# ESP8266_SMD_0603.net
KiCad netlist of a schematic drawn in EAGLE
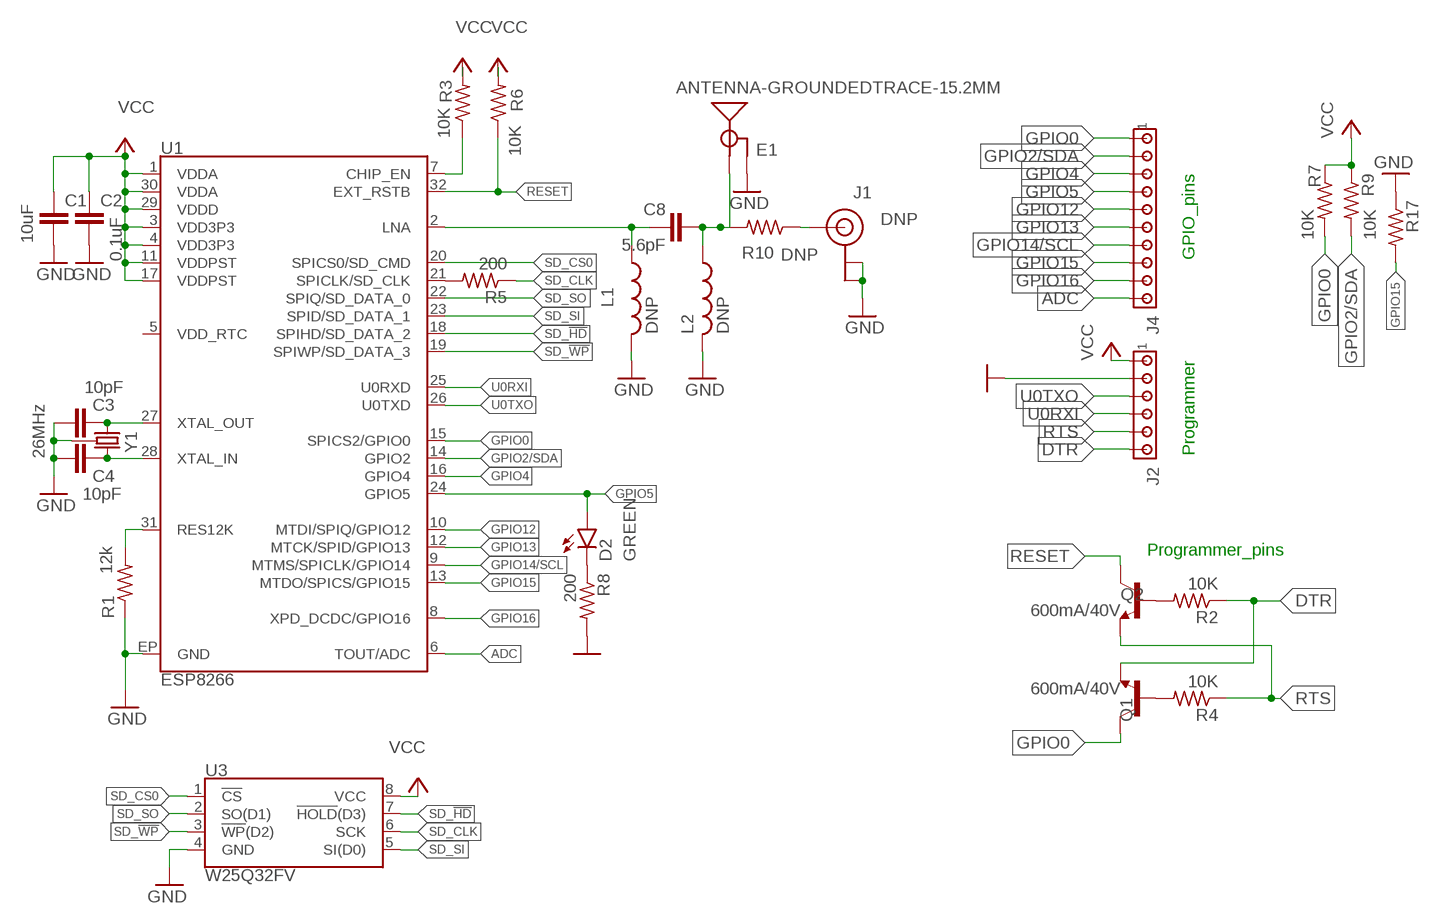
[diagram p0: schematic, sheet 1]

(export (version "E")
  (design (tool "Eeschema 10.0.6"))
  (components
    (comp (ref "C1")
      (value "10uF")
      (footprint "eagle-import:C0603")
      (libsource (lib "eagle-import") (part "resistor_C-EUC0603"))
    )
    (comp (ref "C2")
      (value "0.1uF")
      (footprint "eagle-import:C0603")
      (libsource (lib "eagle-import") (part "resistor_C-EUC0603"))
    )
    (comp (ref "C3")
      (value "10pF")
      (footprint "eagle-import:C0603")
      (libsource (lib "eagle-import") (part "C-EUC0603"))
    )
    (comp (ref "C4")
      (value "10pF")
      (footprint "eagle-import:C0603")
      (libsource (lib "eagle-import") (part "C-EUC0603"))
    )
    (comp (ref "C8")
      (value "5.6pF")
      (footprint "eagle-import:C0603")
      (libsource (lib "eagle-import") (part "C-EUC0603"))
    )
    (comp (ref "D2")
      (value "GREEN")
      (footprint "eagle-import:LED-0603")
      (libsource (lib "eagle-import") (part "LED-GREEN0603"))
    )
    (comp (ref "E1")
      (value "ANTENNA-GROUNDEDTRACE-15.2MM")
      (footprint "eagle-import:TRACE_ANTENNA_2.4GHZ_15.2MM")
      (libsource (lib "eagle-import") (part "ANTENNA-GROUNDEDTRACE-15.2MM"))
    )
    (comp (ref "J1")
      (value "DNP")
      (footprint "eagle-import:U.FL")
      (libsource (lib "eagle-import") (part "U.FL"))
    )
    (comp (ref "J2")
      (value "MTA06-100")
      (footprint "eagle-import:10X06MTA")
      (libsource (lib "eagle-import") (part "MTA06-100"))
    )
    (comp (ref "J4")
      (value "MTA10-100")
      (footprint "eagle-import:10X10MTA")
      (libsource (lib "eagle-import") (part "MTA10-100"))
    )
    (comp (ref "L1")
      (value "DNP")
      (footprint "eagle-import:L0603")
      (libsource (lib "eagle-import") (part "L-USL0603"))
    )
    (comp (ref "L2")
      (value "DNP")
      (footprint "eagle-import:L0603")
      (libsource (lib "eagle-import") (part "L-USL0603"))
    )
    (comp (ref "Q1")
      (value "600mA/40V")
      (footprint "eagle-import:SOT23-3")
      (libsource (lib "eagle-import") (part "TRANS_NPN-MMBT2222AL"))
    )
    (comp (ref "Q2")
      (value "600mA/40V")
      (footprint "eagle-import:SOT23-3")
      (libsource (lib "eagle-import") (part "TRANS_NPN-MMBT2222AL"))
    )
    (comp (ref "R1")
      (value "12k")
      (footprint "eagle-import:R0603")
      (libsource (lib "eagle-import") (part "R-US_R0603"))
    )
    (comp (ref "R2")
      (value "10K")
      (footprint "eagle-import:R0603")
      (libsource (lib "eagle-import") (part "R-US_R0603"))
    )
    (comp (ref "R3")
      (value "10K")
      (footprint "eagle-import:R0603")
      (libsource (lib "eagle-import") (part "R-US_R0603"))
    )
    (comp (ref "R4")
      (value "10K")
      (footprint "eagle-import:R0603")
      (libsource (lib "eagle-import") (part "R-US_R0603"))
    )
    (comp (ref "R5")
      (value "200")
      (footprint "eagle-import:R0603")
      (libsource (lib "eagle-import") (part "R-US_R0603"))
    )
    (comp (ref "R6")
      (value "10K")
      (footprint "eagle-import:R0603")
      (libsource (lib "eagle-import") (part "R-US_R0603"))
    )
    (comp (ref "R7")
      (value "10K")
      (footprint "eagle-import:R0603")
      (libsource (lib "eagle-import") (part "R-US_R0603"))
    )
    (comp (ref "R8")
      (value "200")
      (footprint "eagle-import:R0603")
      (libsource (lib "eagle-import") (part "R-US_R0603"))
    )
    (comp (ref "R9")
      (value "10K")
      (footprint "eagle-import:R0603")
      (libsource (lib "eagle-import") (part "R-US_R0603"))
    )
    (comp (ref "R10")
      (value "DNP")
      (footprint "eagle-import:R0603")
      (libsource (lib "eagle-import") (part "R-US_R0603"))
    )
    (comp (ref "R17")
      (value "10K")
      (footprint "eagle-import:R0603")
      (libsource (lib "eagle-import") (part "R-US_R0603"))
    )
    (comp (ref "U1")
      (value "ESP8266")
      (footprint "eagle-import:QFN32")
      (libsource (lib "eagle-import") (part "ESP8266"))
    )
    (comp (ref "U3")
      (value "W25Q32FV")
      (footprint "eagle-import:SOIC-8")
      (libsource (lib "eagle-import") (part "W25Q32FVSS"))
    )
    (comp (ref "Y1")
      (value "26MHz")
      (footprint "eagle-import:CRYSTAL-SMD-3.2X2.5")
      (libsource (lib "eagle-import") (part "CRYSTAL-GROUNDED3.2X2.5"))
    )
  )
  (nets
    (net (code "1") (name "/SD_~{HD}") (class "Default")
      (node (ref "U1") (pin "18") (pinfunction "SPIHD/SD_DATA_2_18") (pintype "bidirectional"))
      (node (ref "U3") (pin "7") (pinfunction "~{HOLD}(D3)_7") (pintype "bidirectional"))
    )
    (net (code "2") (name "/SD_~{WP}") (class "Default")
      (node (ref "U1") (pin "19") (pinfunction "SPIWP/SD_DATA_3_19") (pintype "bidirectional"))
      (node (ref "U3") (pin "3") (pinfunction "~{WP}(D2)_3") (pintype "bidirectional"))
    )
    (net (code "3") (name "ADC") (class "Default")
      (node (ref "J4") (pin "10") (pinfunction "10_10") (pintype "passive"))
      (node (ref "U1") (pin "6") (pinfunction "TOUT/ADC_6") (pintype "bidirectional"))
    )
    (net (code "4") (name "DTR") (class "Default")
      (node (ref "J2") (pin "6") (pinfunction "6_6") (pintype "passive"))
      (node (ref "Q1") (pin "2") (pinfunction "E_2") (pintype "passive"))
      (node (ref "R2") (pin "1") (pinfunction "1_1") (pintype "passive"))
    )
    (net (code "5") (name "GND") (class "Default")
      (node (ref "C1") (pin "2") (pinfunction "2_2") (pintype "passive"))
      (node (ref "C2") (pin "2") (pinfunction "2_2") (pintype "passive"))
      (node (ref "C3") (pin "1") (pinfunction "1_1") (pintype "passive"))
      (node (ref "C4") (pin "1") (pinfunction "1_1") (pintype "passive"))
      (node (ref "E1") (pin "GND") (pinfunction "GND_GND") (pintype "bidirectional"))
      (node (ref "J1") (pin "P$1") (pinfunction "GND_P$1") (pintype "bidirectional"))
      (node (ref "J1") (pin "P$2") (pinfunction "GND_P$2") (pintype "bidirectional"))
      (node (ref "J2") (pin "2") (pinfunction "2_2") (pintype "passive"))
      (node (ref "L1") (pin "2") (pinfunction "2_2") (pintype "passive"))
      (node (ref "L2") (pin "2") (pinfunction "2_2") (pintype "passive"))
      (node (ref "R1") (pin "1") (pinfunction "1_1") (pintype "passive"))
      (node (ref "R17") (pin "1") (pinfunction "1_1") (pintype "passive"))
      (node (ref "R8") (pin "2") (pinfunction "2_2") (pintype "passive"))
      (node (ref "U1") (pin "EP") (pinfunction "GND_EP") (pintype "bidirectional"))
      (node (ref "U3") (pin "4") (pinfunction "GND_4") (pintype "bidirectional"))
      (node (ref "Y1") (pin "2") (pinfunction "GND_2") (pintype "passive"))
      (node (ref "Y1") (pin "4") (pinfunction "GND_4") (pintype "passive"))
    )
    (net (code "6") (name "GPIO0") (class "Default")
      (node (ref "J4") (pin "1") (pinfunction "1_1") (pintype "passive"))
      (node (ref "Q1") (pin "3") (pinfunction "C_3") (pintype "passive"))
      (node (ref "R7") (pin "2") (pinfunction "2_2") (pintype "passive"))
      (node (ref "U1") (pin "15") (pinfunction "SPICS2/GPIO0_15") (pintype "bidirectional"))
    )
    (net (code "7") (name "GPIO2{slash}SDA") (class "Default")
      (node (ref "J4") (pin "2") (pinfunction "2_2") (pintype "passive"))
      (node (ref "R9") (pin "2") (pinfunction "2_2") (pintype "passive"))
      (node (ref "U1") (pin "14") (pinfunction "GPIO2_14") (pintype "bidirectional"))
    )
    (net (code "8") (name "GPIO4") (class "Default")
      (node (ref "J4") (pin "3") (pinfunction "3_3") (pintype "passive"))
      (node (ref "U1") (pin "16") (pinfunction "GPIO4_16") (pintype "bidirectional"))
    )
    (net (code "9") (name "GPIO5") (class "Default")
      (node (ref "D2") (pin "A") (pinfunction "A_A") (pintype "passive"))
      (node (ref "J4") (pin "4") (pinfunction "4_4") (pintype "passive"))
      (node (ref "U1") (pin "24") (pinfunction "GPIO5_24") (pintype "bidirectional"))
    )
    (net (code "10") (name "GPIO12") (class "Default")
      (node (ref "J4") (pin "5") (pinfunction "5_5") (pintype "passive"))
      (node (ref "U1") (pin "10") (pinfunction "MTDI/SPIQ/GPIO12_10") (pintype "bidirectional"))
    )
    (net (code "11") (name "GPIO13") (class "Default")
      (node (ref "J4") (pin "6") (pinfunction "6_6") (pintype "passive"))
      (node (ref "U1") (pin "12") (pinfunction "MTCK/SPID/GPIO13_12") (pintype "bidirectional"))
    )
    (net (code "12") (name "GPIO14{slash}SCL") (class "Default")
      (node (ref "J4") (pin "7") (pinfunction "7_7") (pintype "passive"))
      (node (ref "U1") (pin "9") (pinfunction "MTMS/SPICLK/GPIO14_9") (pintype "bidirectional"))
    )
    (net (code "13") (name "GPIO15") (class "Default")
      (node (ref "J4") (pin "8") (pinfunction "8_8") (pintype "passive"))
      (node (ref "R17") (pin "2") (pinfunction "2_2") (pintype "passive"))
      (node (ref "U1") (pin "13") (pinfunction "MTDO/SPICS/GPIO15_13") (pintype "bidirectional"))
    )
    (net (code "14") (name "GPIO16") (class "Default")
      (node (ref "J4") (pin "9") (pinfunction "9_9") (pintype "passive"))
      (node (ref "U1") (pin "8") (pinfunction "XPD_DCDC/GPIO16_8") (pintype "bidirectional"))
    )
    (net (code "15") (name "Net-(D2-PadC)") (class "Default")
      (node (ref "D2") (pin "C") (pinfunction "C_C") (pintype "passive"))
      (node (ref "R8") (pin "1") (pinfunction "1_1") (pintype "passive"))
    )
    (net (code "16") (name "Net-(E1-SIGNAL)") (class "Default")
      (node (ref "C8") (pin "2") (pinfunction "2_2") (pintype "passive"))
      (node (ref "E1") (pin "ANT") (pinfunction "SIGNAL_ANT") (pintype "bidirectional"))
      (node (ref "L2") (pin "1") (pinfunction "1_1") (pintype "passive"))
      (node (ref "R10") (pin "2") (pinfunction "2_2") (pintype "passive"))
    )
    (net (code "17") (name "Net-(J1-SIGNAL)") (class "Default")
      (node (ref "J1") (pin "P$3") (pinfunction "SIGNAL_P$3") (pintype "bidirectional"))
      (node (ref "R10") (pin "1") (pinfunction "1_1") (pintype "passive"))
    )
    (net (code "18") (name "Net-(Q1-B)") (class "Default")
      (node (ref "Q1") (pin "1") (pinfunction "B_1") (pintype "passive"))
      (node (ref "R4") (pin "2") (pinfunction "2_2") (pintype "passive"))
    )
    (net (code "19") (name "Net-(Q2-B)") (class "Default")
      (node (ref "Q2") (pin "1") (pinfunction "B_1") (pintype "passive"))
      (node (ref "R2") (pin "2") (pinfunction "2_2") (pintype "passive"))
    )
    (net (code "20") (name "Net-(U1-CHIP_EN)") (class "Default")
      (node (ref "R3") (pin "1") (pinfunction "1_1") (pintype "passive"))
      (node (ref "U1") (pin "7") (pinfunction "CHIP_EN_7") (pintype "bidirectional"))
    )
    (net (code "21") (name "Net-(U1-LNA)") (class "Default")
      (node (ref "C8") (pin "1") (pinfunction "1_1") (pintype "passive"))
      (node (ref "L1") (pin "1") (pinfunction "1_1") (pintype "passive"))
      (node (ref "U1") (pin "2") (pinfunction "LNA_2") (pintype "bidirectional"))
    )
    (net (code "22") (name "Net-(U1-RES12K)") (class "Default")
      (node (ref "R1") (pin "2") (pinfunction "2_2") (pintype "passive"))
      (node (ref "U1") (pin "31") (pinfunction "RES12K_31") (pintype "bidirectional"))
    )
    (net (code "23") (name "Net-(U1-SPICLK{slash}SD_CLK)") (class "Default")
      (node (ref "R5") (pin "2") (pinfunction "2_2") (pintype "passive"))
      (node (ref "U1") (pin "21") (pinfunction "SPICLK/SD_CLK_21") (pintype "bidirectional"))
    )
    (net (code "24") (name "Net-(U1-XTAL_IN)") (class "Default")
      (node (ref "C4") (pin "2") (pinfunction "2_2") (pintype "passive"))
      (node (ref "U1") (pin "28") (pinfunction "XTAL_IN_28") (pintype "bidirectional"))
      (node (ref "Y1") (pin "3") (pinfunction "2_3") (pintype "passive"))
    )
    (net (code "25") (name "Net-(U1-XTAL_OUT)") (class "Default")
      (node (ref "C3") (pin "2") (pinfunction "2_2") (pintype "passive"))
      (node (ref "U1") (pin "27") (pinfunction "XTAL_OUT_27") (pintype "bidirectional"))
      (node (ref "Y1") (pin "1") (pinfunction "1_1") (pintype "passive"))
    )
    (net (code "26") (name "RESET") (class "Default")
      (node (ref "Q2") (pin "3") (pinfunction "C_3") (pintype "passive"))
      (node (ref "R6") (pin "1") (pinfunction "1_1") (pintype "passive"))
      (node (ref "U1") (pin "32") (pinfunction "EXT_RSTB_32") (pintype "bidirectional"))
    )
    (net (code "27") (name "RTS") (class "Default")
      (node (ref "J2") (pin "5") (pinfunction "5_5") (pintype "passive"))
      (node (ref "Q2") (pin "2") (pinfunction "E_2") (pintype "passive"))
      (node (ref "R4") (pin "1") (pinfunction "1_1") (pintype "passive"))
    )
    (net (code "28") (name "SD_CLK") (class "Default")
      (node (ref "R5") (pin "1") (pinfunction "1_1") (pintype "passive"))
      (node (ref "U3") (pin "6") (pinfunction "SCK_6") (pintype "bidirectional"))
    )
    (net (code "29") (name "SD_CS0") (class "Default")
      (node (ref "U1") (pin "20") (pinfunction "SPICS0/SD_CMD_20") (pintype "bidirectional"))
      (node (ref "U3") (pin "1") (pinfunction "~{CS}_1") (pintype "bidirectional"))
    )
    (net (code "30") (name "SD_SI") (class "Default")
      (node (ref "U1") (pin "23") (pinfunction "SPID/SD_DATA_1_23") (pintype "bidirectional"))
      (node (ref "U3") (pin "5") (pinfunction "SI(D0)_5") (pintype "bidirectional"))
    )
    (net (code "31") (name "SD_SO") (class "Default")
      (node (ref "U1") (pin "22") (pinfunction "SPIQ/SD_DATA_0_22") (pintype "bidirectional"))
      (node (ref "U3") (pin "2") (pinfunction "SO(D1)_2") (pintype "bidirectional"))
    )
    (net (code "32") (name "U0RXI") (class "Default")
      (node (ref "J2") (pin "4") (pinfunction "4_4") (pintype "passive"))
      (node (ref "U1") (pin "25") (pinfunction "U0RXD_25") (pintype "bidirectional"))
    )
    (net (code "33") (name "U0TXO") (class "Default")
      (node (ref "J2") (pin "3") (pinfunction "3_3") (pintype "passive"))
      (node (ref "U1") (pin "26") (pinfunction "U0TXD_26") (pintype "bidirectional"))
    )
    (net (code "34") (name "VCC") (class "Default")
      (node (ref "C1") (pin "1") (pinfunction "1_1") (pintype "passive"))
      (node (ref "C2") (pin "1") (pinfunction "1_1") (pintype "passive"))
      (node (ref "J2") (pin "1") (pinfunction "1_1") (pintype "passive"))
      (node (ref "R3") (pin "2") (pinfunction "2_2") (pintype "passive"))
      (node (ref "R6") (pin "2") (pinfunction "2_2") (pintype "passive"))
      (node (ref "R7") (pin "1") (pinfunction "1_1") (pintype "passive"))
      (node (ref "R9") (pin "1") (pinfunction "1_1") (pintype "passive"))
      (node (ref "U1") (pin "1") (pinfunction "VDDA_1") (pintype "bidirectional"))
      (node (ref "U1") (pin "11") (pinfunction "VDDPST_11") (pintype "bidirectional"))
      (node (ref "U1") (pin "17") (pinfunction "VDDPST_17") (pintype "bidirectional"))
      (node (ref "U1") (pin "29") (pinfunction "VDDD_29") (pintype "bidirectional"))
      (node (ref "U1") (pin "3") (pinfunction "VDD3P3_3") (pintype "bidirectional"))
      (node (ref "U1") (pin "30") (pinfunction "VDDA_30") (pintype "bidirectional"))
      (node (ref "U1") (pin "4") (pinfunction "VDD3P3_4") (pintype "bidirectional"))
      (node (ref "U3") (pin "8") (pinfunction "VCC_8") (pintype "bidirectional"))
    )
    (net (code "35") (name "unconnected-(U1-VDD_RTC-Pad5)") (class "Default")
      (node (ref "U1") (pin "5") (pinfunction "VDD_RTC_5") (pintype "bidirectional"))
    )
  )
)
